# design.net
KiCad netlist of a schematic drawn in Altium Designer
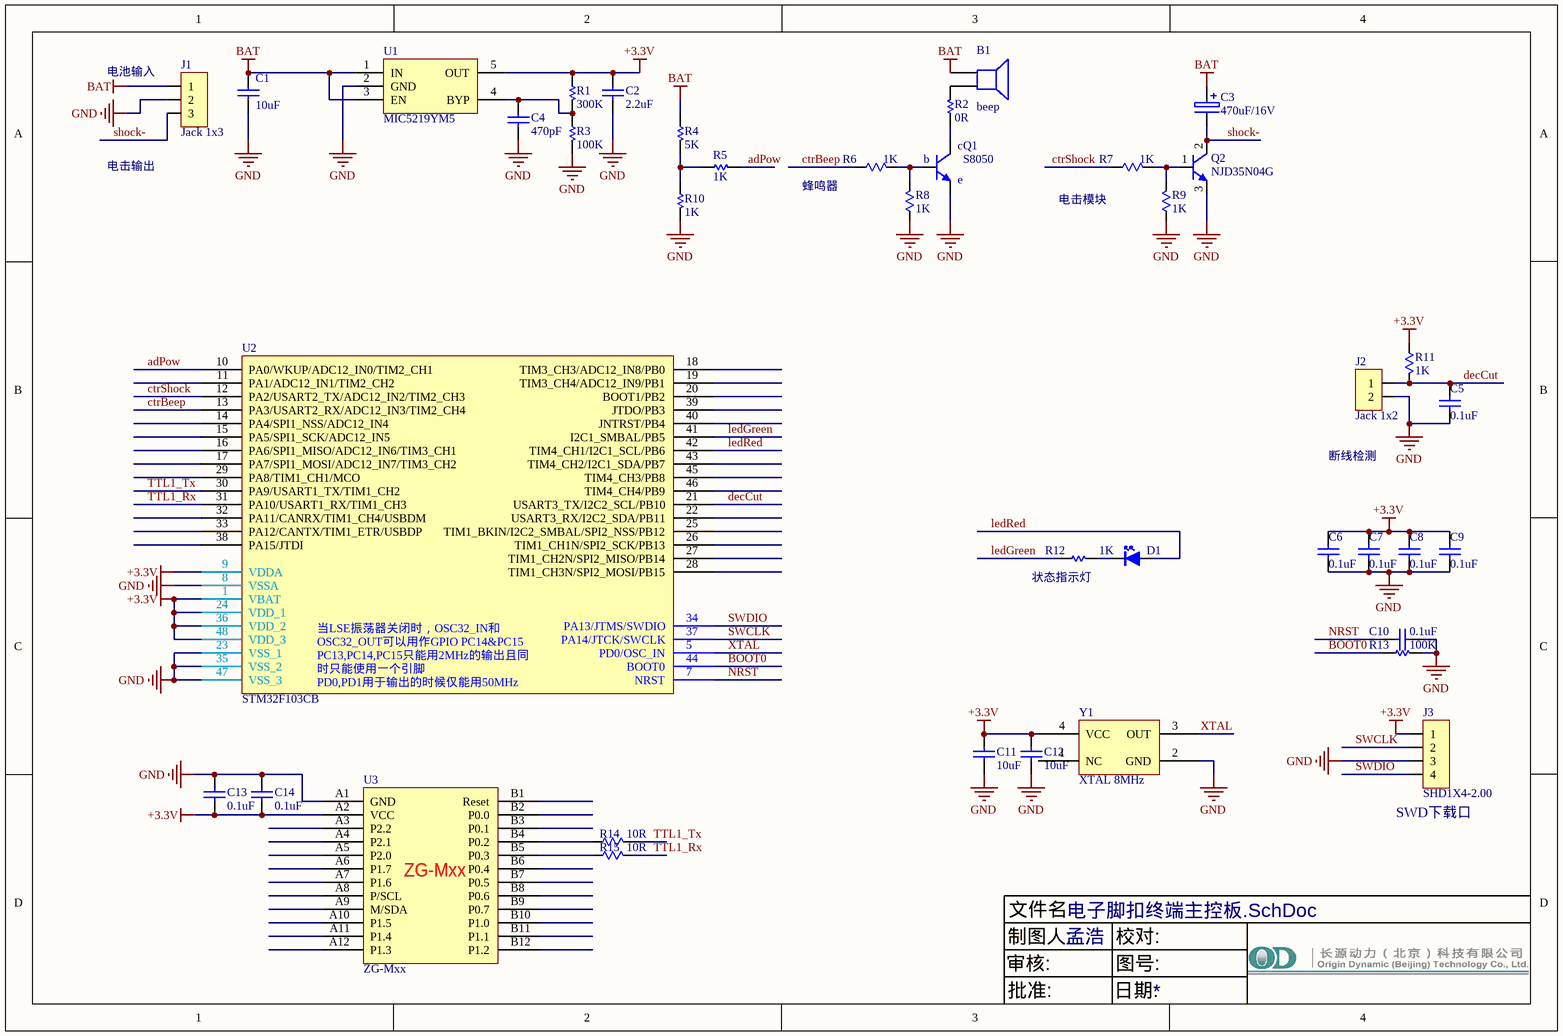
[diagram p0: 电子脚扣终端主控板.SchDoc]

(export (version "E")
  (design (tool "Eeschema 10.0.6"))
  (components
    (comp (ref "B1")
      (value "beep")
      (footprint "Jk1*2-2.0")
      (description "Loudspeaker")
      (fields (field (name "PUBLISHER") "Altium Limited"))
      (libsource (lib "Miscellaneous Devices") (part "Speaker"))
    )
    (comp (ref "C1") (value "10uF") (footprint "C0603") (libsource (lib "RLCYDF") (part "Cap Semi")))
    (comp (ref "C2")
      (value "2.2uF")
      (footprint "C0603")
      (description "CAP")
      (fields (field (name "PUBLISHER") "Altium Limited"))
      (libsource (lib "Passive Components Class") (part "CAP"))
    )
    (comp (ref "C3") (value "470uF/16V") (footprint "Jk1*2-2.0") (libsource (lib "RLCYDF") (part "Cap Poll")))
    (comp (ref "C4")
      (value "470pF")
      (footprint "C0603")
      (description "CAP")
      (fields (field (name "PUBLISHER") "Altium Limited"))
      (libsource (lib "Passive Components Class") (part "CAP"))
    )
    (comp (ref "C5") (value "0.1uF") (footprint "C0603") (libsource (lib "RLCYDF") (part "Cap Semi")))
    (comp (ref "C6") (value "0.1uF") (footprint "C0603") (libsource (lib "RLCYDF") (part "Cap Semi")))
    (comp (ref "C7") (value "0.1uF") (footprint "C0603") (libsource (lib "RLCYDF") (part "Cap Semi")))
    (comp (ref "C8") (value "0.1uF") (footprint "C0603") (libsource (lib "RLCYDF") (part "Cap Semi")))
    (comp (ref "C9") (value "0.1uF") (footprint "C0603") (libsource (lib "RLCYDF") (part "Cap Semi")))
    (comp (ref "C10") (value "0.1uF") (footprint "C0603") (libsource (lib "RLCYDF") (part "Cap Semi")))
    (comp (ref "C11") (value "10uF") (footprint "C0603") (libsource (lib "RLCYDF") (part "Cap Semi")))
    (comp (ref "C12") (value "10uF") (footprint "C0603") (libsource (lib "RLCYDF") (part "Cap Semi")))
    (comp (ref "C13")
      (value "0.1uF")
      (footprint "C0603")
      (description "Capacitor")
      (fields (field (name "PUBLISHER") "Altium Limited"))
      (libsource (lib "Miscellaneous Devices") (part "Cap"))
    )
    (comp (ref "C14")
      (value "0.1uF")
      (footprint "C0603")
      (description "Capacitor")
      (fields (field (name "PUBLISHER") "Altium Limited"))
      (libsource (lib "Miscellaneous Devices") (part "Cap"))
    )
    (comp (ref "D1")
      (value "LED")
      (footprint "Led-D3")
      (libsource (lib "Passive Components Class") (part "LED"))
    )
    (comp (ref "J1")
      (value "Jack 1x3")
      (footprint "Jk1*3-2.0")
      (description "插座")
      (libsource (lib "Connector") (part "Jack 1x3"))
    )
    (comp (ref "J2")
      (value "Jack 1x2")
      (footprint "Jk1*2-2.0")
      (description "插座")
      (libsource (lib "Connector") (part "Jack 1x2"))
    )
    (comp (ref "J3")
      (value "SHD1X4-2.00")
      (footprint "Jk1*4-2.0")
      (libsource (lib "Connector Class") (part "HEADER1X4"))
    )
    (comp (ref "Q1")
      (value "S8050")
      (footprint "chip:SOT-23")
      (description "NPN triode, 0.5A Max")
      (libsource (lib "RLCYDF") (part "S8050"))
    )
    (comp (ref "Q2") (value "NJD35N04G") (footprint "TO-252") (libsource (lib "ArmArmor") (part "MJD122")))
    (comp (ref "R1") (value "300K") (footprint "R0603") (libsource (lib "RLCYDF") (part "Res")))
    (comp (ref "R2") (value "0R") (footprint "R0603") (libsource (lib "RLCYDF") (part "Res")))
    (comp (ref "R3") (value "100K") (footprint "R0603") (libsource (lib "RLCYDF") (part "Res")))
    (comp (ref "R4") (value "5K") (footprint "R0603") (libsource (lib "RLCYDF") (part "Res")))
    (comp (ref "R5") (value "1K") (footprint "R0603") (libsource (lib "RLCYDF") (part "Res")))
    (comp (ref "R6")
      (value "1K")
      (footprint "R0603")
      (description "Resistor")
      (fields (field (name "PUBLISHER") "Altium Limited"))
      (libsource (lib "Passive Components Class") (part "RES"))
    )
    (comp (ref "R7")
      (value "1K")
      (footprint "R0603")
      (description "Resistor")
      (fields (field (name "PUBLISHER") "Altium Limited"))
      (libsource (lib "Passive Components Class") (part "RES"))
    )
    (comp (ref "R8")
      (value "1K")
      (footprint "R0603")
      (description "Resistor")
      (fields (field (name "PUBLISHER") "Altium Limited"))
      (libsource (lib "Passive Components Class") (part "RES"))
    )
    (comp (ref "R9")
      (value "1K")
      (footprint "R0603")
      (description "Resistor")
      (fields (field (name "PUBLISHER") "Altium Limited"))
      (libsource (lib "Passive Components Class") (part "RES"))
    )
    (comp (ref "R10") (value "1K") (footprint "R0603") (libsource (lib "RLCYDF") (part "Res")))
    (comp (ref "R11")
      (value "1K")
      (footprint "R0603")
      (description "Resistor")
      (fields (field (name "PUBLISHER") "Altium Limited"))
      (libsource (lib "Passive Components Class") (part "RES"))
    )
    (comp (ref "R12") (value "1K") (footprint "R0603") (libsource (lib "RLCYDF") (part "Res")))
    (comp (ref "R13") (value "100K") (footprint "R0603") (libsource (lib "RLCYDF") (part "Res")))
    (comp (ref "R14")
      (value "10R")
      (footprint "R0603")
      (description "Resistor")
      (fields (field (name "PUBLISHER") "Altium Limited"))
      (libsource (lib "UP-Robot") (part "Res"))
    )
    (comp (ref "R15")
      (value "10R")
      (footprint "R0603")
      (description "Resistor")
      (fields (field (name "PUBLISHER") "Altium Limited"))
      (libsource (lib "UP-Robot") (part "Res"))
    )
    (comp (ref "U1") (value "MIC5219YM5") (footprint "SOT-23-5") (libsource (lib "Power") (part "MIC5205")))
    (comp (ref "U2") (value "STM32F103CB") (footprint "LQF48") (libsource (lib "stm32") (part "STM32F103Cx")))
    (comp (ref "U3") (value "ZG-Mxx") (footprint "ZG-M0") (libsource (lib "ZG-Mxx") (part "ZG-Mxx")))
    (comp (ref "Y1") (value "XTAL 8MHz") (footprint "XTAL5032") (libsource (lib "Mic2805") (part "XTAL")))
  )
  (nets
    (net (code "1") (name "+3.3V") (class "Default")
      (node (ref "C11") (pin "2") (pinfunction "2_2") (pintype "passive"))
      (node (ref "C12") (pin "2") (pinfunction "2_2") (pintype "passive"))
      (node (ref "C13") (pin "1") (pinfunction "1_1") (pintype "passive"))
      (node (ref "C14") (pin "1") (pinfunction "1_1") (pintype "passive"))
      (node (ref "C2") (pin "1") (pinfunction "1_1") (pintype "passive"))
      (node (ref "C6") (pin "1") (pinfunction "1_1") (pintype "passive"))
      (node (ref "C7") (pin "1") (pinfunction "1_1") (pintype "passive"))
      (node (ref "C8") (pin "1") (pinfunction "1_1") (pintype "passive"))
      (node (ref "C9") (pin "1") (pinfunction "1_1") (pintype "passive"))
      (node (ref "J3") (pin "1") (pinfunction "1_1") (pintype "passive"))
      (node (ref "R1") (pin "1") (pinfunction "1_1") (pintype "passive"))
      (node (ref "R11") (pin "1") (pinfunction "1_1") (pintype "passive"))
      (node (ref "U1") (pin "5") (pinfunction "OUT_5") (pintype "passive"))
      (node (ref "U2") (pin "1") (pinfunction "VBAT_1") (pintype "power_in"))
      (node (ref "U2") (pin "24") (pinfunction "VDD_1_24") (pintype "power_in"))
      (node (ref "U2") (pin "36") (pinfunction "VDD_2_36") (pintype "power_in"))
      (node (ref "U2") (pin "48") (pinfunction "VDD_3_48") (pintype "power_in"))
      (node (ref "U2") (pin "9") (pinfunction "VDDA_9") (pintype "power_in"))
      (node (ref "U3") (pin "A2") (pinfunction "VCC_A2") (pintype "passive"))
      (node (ref "Y1") (pin "4") (pinfunction "VCC_4") (pintype "passive"))
    )
    (net (code "2") (name "/BOOT0") (class "Default")
      (node (ref "R13") (pin "1") (pinfunction "1_1") (pintype "passive"))
      (node (ref "U2") (pin "44") (pinfunction "BOOT0_44") (pintype "passive"))
    )
    (net (code "3") (name "/NRST") (class "Default")
      (node (ref "C10") (pin "1") (pinfunction "1_1") (pintype "passive"))
      (node (ref "U2") (pin "7") (pinfunction "NRST_7") (pintype "passive"))
    )
    (net (code "4") (name "/SWCLK") (class "Default")
      (node (ref "J3") (pin "2") (pinfunction "2_2") (pintype "passive"))
      (node (ref "U2") (pin "37") (pinfunction "PA14/JTCK/SWCLK_37") (pintype "passive"))
    )
    (net (code "5") (name "/SWDIO") (class "Default")
      (node (ref "J3") (pin "4") (pinfunction "4_4") (pintype "passive"))
      (node (ref "U2") (pin "34") (pinfunction "PA13/JTMS/SWDIO_34") (pintype "passive"))
    )
    (net (code "6") (name "/TTL1_Rx") (class "Default")
      (node (ref "R15") (pin "1") (pinfunction "1_1") (pintype "passive"))
      (node (ref "U2") (pin "31") (pinfunction "PA10/USART1_RX/TIM1_CH3_31") (pintype "passive"))
    )
    (net (code "7") (name "/TTL1_Tx") (class "Default")
      (node (ref "R14") (pin "1") (pinfunction "1_1") (pintype "passive"))
      (node (ref "U2") (pin "30") (pinfunction "PA9/USART1_TX/TIM1_CH2_30") (pintype "passive"))
    )
    (net (code "8") (name "/XTAL") (class "Default")
      (node (ref "U2") (pin "5") (pinfunction "PD0/OSC_IN_5") (pintype "passive"))
      (node (ref "Y1") (pin "3") (pinfunction "OUT_3") (pintype "passive"))
    )
    (net (code "9") (name "/adPow") (class "Default")
      (node (ref "R5") (pin "2") (pinfunction "2_2") (pintype "passive"))
      (node (ref "U2") (pin "10") (pinfunction "PA0/WKUP/ADC12_IN0/TIM2_CH1_10") (pintype "passive"))
    )
    (net (code "10") (name "/ctrBeep") (class "Default")
      (node (ref "R6") (pin "1") (pinfunction "1_1") (pintype "passive"))
      (node (ref "U2") (pin "13") (pinfunction "PA3/USART2_RX/ADC12_IN3/TIM2_CH4_13") (pintype "passive"))
    )
    (net (code "11") (name "/ctrShock") (class "Default")
      (node (ref "R7") (pin "1") (pinfunction "1_1") (pintype "passive"))
      (node (ref "U2") (pin "12") (pinfunction "PA2/USART2_TX/ADC12_IN2/TIM2_CH3_12") (pintype "passive"))
    )
    (net (code "12") (name "/decCut") (class "Default")
      (node (ref "C5") (pin "1") (pinfunction "1_1") (pintype "passive"))
      (node (ref "J2") (pin "1") (pinfunction "1_1") (pintype "passive"))
      (node (ref "R11") (pin "2") (pinfunction "2_2") (pintype "passive"))
      (node (ref "U2") (pin "21") (pinfunction "USART3_TX/I2C2_SCL/PB10_21") (pintype "passive"))
    )
    (net (code "13") (name "/ledGreen") (class "Default")
      (node (ref "R12") (pin "1") (pinfunction "1_1") (pintype "passive"))
      (node (ref "U2") (pin "41") (pinfunction "I2C1_SMBAL/PB5_41") (pintype "passive"))
    )
    (net (code "14") (name "/ledRed") (class "Default")
      (node (ref "D1") (pin "1") (pinfunction "A_1") (pintype "passive"))
      (node (ref "U2") (pin "42") (pinfunction "TIM4_CH1/I2C1_SCL/PB6_42") (pintype "passive"))
    )
    (net (code "15") (name "/shock-") (class "Default")
      (node (ref "C3") (pin "2") (pinfunction "2_2") (pintype "passive"))
      (node (ref "J1") (pin "3") (pinfunction "3_3") (pintype "passive"))
      (node (ref "Q2") (pin "2") (pinfunction "C_2") (pintype "passive"))
    )
    (net (code "16") (name "BAT") (class "Default")
      (node (ref "B1") (pin "1") (pinfunction "1_1") (pintype "passive"))
      (node (ref "C1") (pin "2") (pinfunction "2_2") (pintype "passive"))
      (node (ref "C3") (pin "1") (pinfunction "1_1") (pintype "passive"))
      (node (ref "J1") (pin "1") (pinfunction "1_1") (pintype "passive"))
      (node (ref "R4") (pin "1") (pinfunction "1_1") (pintype "passive"))
      (node (ref "U1") (pin "1") (pinfunction "IN_1") (pintype "passive"))
      (node (ref "U1") (pin "3") (pinfunction "EN_3") (pintype "passive"))
    )
    (net (code "17") (name "GND") (class "Default")
      (node (ref "C1") (pin "1") (pinfunction "1_1") (pintype "passive"))
      (node (ref "C10") (pin "2") (pinfunction "2_2") (pintype "passive"))
      (node (ref "C11") (pin "1") (pinfunction "1_1") (pintype "passive"))
      (node (ref "C12") (pin "1") (pinfunction "1_1") (pintype "passive"))
      (node (ref "C13") (pin "2") (pinfunction "2_2") (pintype "passive"))
      (node (ref "C14") (pin "2") (pinfunction "2_2") (pintype "passive"))
      (node (ref "C2") (pin "2") (pinfunction "2_2") (pintype "passive"))
      (node (ref "C4") (pin "2") (pinfunction "2_2") (pintype "passive"))
      (node (ref "C5") (pin "2") (pinfunction "2_2") (pintype "passive"))
      (node (ref "C6") (pin "2") (pinfunction "2_2") (pintype "passive"))
      (node (ref "C7") (pin "2") (pinfunction "2_2") (pintype "passive"))
      (node (ref "C8") (pin "2") (pinfunction "2_2") (pintype "passive"))
      (node (ref "C9") (pin "2") (pinfunction "2_2") (pintype "passive"))
      (node (ref "J1") (pin "2") (pinfunction "2_2") (pintype "passive"))
      (node (ref "J2") (pin "2") (pinfunction "2_2") (pintype "passive"))
      (node (ref "J3") (pin "3") (pinfunction "3_3") (pintype "passive"))
      (node (ref "Q1") (pin "2") (pinfunction "e_2") (pintype "passive"))
      (node (ref "Q2") (pin "3") (pinfunction "E_3") (pintype "passive"))
      (node (ref "R10") (pin "2") (pinfunction "2_2") (pintype "passive"))
      (node (ref "R13") (pin "2") (pinfunction "2_2") (pintype "passive"))
      (node (ref "R3") (pin "2") (pinfunction "2_2") (pintype "passive"))
      (node (ref "R8") (pin "1") (pinfunction "1_1") (pintype "passive"))
      (node (ref "R9") (pin "1") (pinfunction "1_1") (pintype "passive"))
      (node (ref "U1") (pin "2") (pinfunction "GND_2") (pintype "passive"))
      (node (ref "U2") (pin "23") (pinfunction "VSS_1_23") (pintype "power_in"))
      (node (ref "U2") (pin "35") (pinfunction "VSS_2_35") (pintype "power_in"))
      (node (ref "U2") (pin "47") (pinfunction "VSS_3_47") (pintype "power_in"))
      (node (ref "U2") (pin "8") (pinfunction "VSSA_8") (pintype "power_in"))
      (node (ref "U3") (pin "A1") (pinfunction "GND_A1") (pintype "passive"))
      (node (ref "Y1") (pin "2") (pinfunction "GND_2") (pintype "passive"))
    )
    (net (code "18") (name "Net-(B1-Pad2)") (class "Default")
      (node (ref "B1") (pin "2") (pinfunction "2_2") (pintype "passive"))
      (node (ref "R2") (pin "2") (pinfunction "2_2") (pintype "passive"))
    )
    (net (code "19") (name "Net-(D1-K)") (class "Default")
      (node (ref "D1") (pin "2") (pinfunction "K_2") (pintype "passive"))
      (node (ref "R12") (pin "2") (pinfunction "2_2") (pintype "passive"))
    )
    (net (code "20") (name "Net-(Q1-b)") (class "Default")
      (node (ref "Q1") (pin "1") (pinfunction "b_1") (pintype "passive"))
      (node (ref "R6") (pin "2") (pinfunction "2_2") (pintype "passive"))
      (node (ref "R8") (pin "2") (pinfunction "2_2") (pintype "passive"))
    )
    (net (code "21") (name "Net-(Q1-c)") (class "Default")
      (node (ref "Q1") (pin "3") (pinfunction "c_3") (pintype "passive"))
      (node (ref "R2") (pin "1") (pinfunction "1_1") (pintype "passive"))
    )
    (net (code "22") (name "Net-(Q2-B)") (class "Default")
      (node (ref "Q2") (pin "1") (pinfunction "B_1") (pintype "passive"))
      (node (ref "R7") (pin "2") (pinfunction "2_2") (pintype "passive"))
      (node (ref "R9") (pin "2") (pinfunction "2_2") (pintype "passive"))
    )
    (net (code "23") (name "Net-(R10-Pad1)") (class "Default")
      (node (ref "R10") (pin "1") (pinfunction "1_1") (pintype "passive"))
      (node (ref "R4") (pin "2") (pinfunction "2_2") (pintype "passive"))
      (node (ref "R5") (pin "1") (pinfunction "1_1") (pintype "passive"))
    )
    (net (code "24") (name "Net-(U1-BYP)") (class "Default")
      (node (ref "C4") (pin "1") (pinfunction "1_1") (pintype "passive"))
      (node (ref "R1") (pin "2") (pinfunction "2_2") (pintype "passive"))
      (node (ref "R3") (pin "1") (pinfunction "1_1") (pintype "passive"))
      (node (ref "U1") (pin "4") (pinfunction "BYP_4") (pintype "passive"))
    )
    (net (code "25") (name "Net-(U3-P0.2)") (class "Default")
      (node (ref "R14") (pin "2") (pinfunction "2_2") (pintype "passive"))
      (node (ref "U3") (pin "B4") (pinfunction "P0.2_B4") (pintype "passive"))
    )
    (net (code "26") (name "Net-(U3-P0.3)") (class "Default")
      (node (ref "R15") (pin "2") (pinfunction "2_2") (pintype "passive"))
      (node (ref "U3") (pin "B5") (pinfunction "P0.3_B5") (pintype "passive"))
    )
    (net (code "27") (name "unconnected-(U2-BOOT1{slash}PB2-Pad20)") (class "Default")
      (node (ref "U2") (pin "20") (pinfunction "BOOT1/PB2_20") (pintype "passive"))
    )
    (net (code "28") (name "unconnected-(U2-JNTRST{slash}PB4-Pad40)") (class "Default")
      (node (ref "U2") (pin "40") (pinfunction "JNTRST/PB4_40") (pintype "passive"))
    )
    (net (code "29") (name "unconnected-(U2-JTDO{slash}PB3-Pad39)") (class "Default")
      (node (ref "U2") (pin "39") (pinfunction "JTDO/PB3_39") (pintype "passive"))
    )
    (net (code "30") (name "unconnected-(U2-PA1{slash}ADC12_IN1{slash}TIM2_CH2-Pad11)") (class "Default")
      (node (ref "U2") (pin "11") (pinfunction "PA1/ADC12_IN1/TIM2_CH2_11") (pintype "passive"))
    )
    (net (code "31") (name "unconnected-(U2-PA4{slash}SPI1_NSS{slash}ADC12_IN4-Pad14)") (class "Default")
      (node (ref "U2") (pin "14") (pinfunction "PA4/SPI1_NSS/ADC12_IN4_14") (pintype "passive"))
    )
    (net (code "32") (name "unconnected-(U2-PA5{slash}SPI1_SCK{slash}ADC12_IN5-Pad15)") (class "Default")
      (node (ref "U2") (pin "15") (pinfunction "PA5/SPI1_SCK/ADC12_IN5_15") (pintype "passive"))
    )
    (net (code "33") (name "unconnected-(U2-PA6{slash}SPI1_MISO{slash}ADC12_IN6{slash}TIM3_CH1-Pad16)") (class "Default")
      (node (ref "U2") (pin "16") (pinfunction "PA6/SPI1_MISO/ADC12_IN6/TIM3_CH1_16") (pintype "passive"))
    )
    (net (code "34") (name "unconnected-(U2-PA7{slash}SPI1_MOSI{slash}ADC12_IN7{slash}TIM3_CH2-Pad17)") (class "Default")
      (node (ref "U2") (pin "17") (pinfunction "PA7/SPI1_MOSI/ADC12_IN7/TIM3_CH2_17") (pintype "passive"))
    )
    (net (code "35") (name "unconnected-(U2-PA8{slash}TIM1_CH1{slash}MCO-Pad29)") (class "Default")
      (node (ref "U2") (pin "29") (pinfunction "PA8/TIM1_CH1/MCO_29") (pintype "passive"))
    )
    (net (code "36") (name "unconnected-(U2-PA11{slash}CANRX{slash}TIM1_CH4{slash}USBDM-Pad32)") (class "Default")
      (node (ref "U2") (pin "32") (pinfunction "PA11/CANRX/TIM1_CH4/USBDM_32") (pintype "passive"))
    )
    (net (code "37") (name "unconnected-(U2-PA12{slash}CANTX{slash}TIM1_ETR{slash}USBDP-Pad33)") (class "Default")
      (node (ref "U2") (pin "33") (pinfunction "PA12/CANTX/TIM1_ETR/USBDP_33") (pintype "passive"))
    )
    (net (code "38") (name "unconnected-(U2-PA15{slash}JTDI-Pad38)") (class "Default")
      (node (ref "U2") (pin "38") (pinfunction "PA15/JTDI_38") (pintype "passive"))
    )
    (net (code "39") (name "unconnected-(U2-PC13-TAMPER-RTC-Pad2)") (class "Default")
      (node (ref "U2") (pin "2") (pinfunction "PC13-TAMPER-RTC_2") (pintype "passive"))
    )
    (net (code "40") (name "unconnected-(U2-PC14-OSC32_IN-Pad3)") (class "Default")
      (node (ref "U2") (pin "3") (pinfunction "PC14-OSC32_IN_3") (pintype "passive"))
    )
    (net (code "41") (name "unconnected-(U2-PC15-OSC32_OUT-Pad4)") (class "Default")
      (node (ref "U2") (pin "4") (pinfunction "PC15-OSC32_OUT_4") (pintype "passive"))
    )
    (net (code "42") (name "unconnected-(U2-PD1{slash}OSC_OUT-Pad6)") (class "Default")
      (node (ref "U2") (pin "6") (pinfunction "PD1/OSC_OUT_6") (pintype "passive"))
    )
    (net (code "43") (name "unconnected-(U2-TIM1_BKIN{slash}I2C2_SMBAL{slash}SPI2_NSS{slash}PB12-Pad25)") (class "Default")
      (node (ref "U2") (pin "25") (pinfunction "TIM1_BKIN/I2C2_SMBAL/SPI2_NSS/PB12_25") (pintype "passive"))
    )
    (net (code "44") (name "unconnected-(U2-TIM1_CH1N{slash}SPI2_SCK{slash}PB13-Pad26)") (class "Default")
      (node (ref "U2") (pin "26") (pinfunction "TIM1_CH1N/SPI2_SCK/PB13_26") (pintype "passive"))
    )
    (net (code "45") (name "unconnected-(U2-TIM1_CH2N{slash}SPI2_MISO{slash}PB14-Pad27)") (class "Default")
      (node (ref "U2") (pin "27") (pinfunction "TIM1_CH2N/SPI2_MISO/PB14_27") (pintype "passive"))
    )
    (net (code "46") (name "unconnected-(U2-TIM1_CH3N{slash}SPI2_MOSI{slash}PB15-Pad28)") (class "Default")
      (node (ref "U2") (pin "28") (pinfunction "TIM1_CH3N/SPI2_MOSI/PB15_28") (pintype "passive"))
    )
    (net (code "47") (name "unconnected-(U2-TIM3_CH3{slash}ADC12_IN8{slash}PB0-Pad18)") (class "Default")
      (node (ref "U2") (pin "18") (pinfunction "TIM3_CH3/ADC12_IN8/PB0_18") (pintype "passive"))
    )
    (net (code "48") (name "unconnected-(U2-TIM3_CH4{slash}ADC12_IN9{slash}PB1-Pad19)") (class "Default")
      (node (ref "U2") (pin "19") (pinfunction "TIM3_CH4/ADC12_IN9/PB1_19") (pintype "passive"))
    )
    (net (code "49") (name "unconnected-(U2-TIM4_CH2{slash}I2C1_SDA{slash}PB7-Pad43)") (class "Default")
      (node (ref "U2") (pin "43") (pinfunction "TIM4_CH2/I2C1_SDA/PB7_43") (pintype "passive"))
    )
    (net (code "50") (name "unconnected-(U2-TIM4_CH3{slash}PB8-Pad45)") (class "Default")
      (node (ref "U2") (pin "45") (pinfunction "TIM4_CH3/PB8_45") (pintype "passive"))
    )
    (net (code "51") (name "unconnected-(U2-TIM4_CH4{slash}PB9-Pad46)") (class "Default")
      (node (ref "U2") (pin "46") (pinfunction "TIM4_CH4/PB9_46") (pintype "passive"))
    )
    (net (code "52") (name "unconnected-(U2-USART3_RX{slash}I2C2_SDA{slash}PB11-Pad22)") (class "Default")
      (node (ref "U2") (pin "22") (pinfunction "USART3_RX/I2C2_SDA/PB11_22") (pintype "passive"))
    )
    (net (code "53") (name "unconnected-(U3-M{slash}SDA-PadA9)") (class "Default")
      (node (ref "U3") (pin "A9") (pinfunction "M/SDA_A9") (pintype "passive"))
    )
    (net (code "54") (name "unconnected-(U3-P0.0-PadB2)") (class "Default")
      (node (ref "U3") (pin "B2") (pinfunction "P0.0_B2") (pintype "passive"))
    )
    (net (code "55") (name "unconnected-(U3-P0.1-PadB3)") (class "Default")
      (node (ref "U3") (pin "B3") (pinfunction "P0.1_B3") (pintype "passive"))
    )
    (net (code "56") (name "unconnected-(U3-P0.4-PadB6)") (class "Default")
      (node (ref "U3") (pin "B6") (pinfunction "P0.4_B6") (pintype "passive"))
    )
    (net (code "57") (name "unconnected-(U3-P0.5-PadB7)") (class "Default")
      (node (ref "U3") (pin "B7") (pinfunction "P0.5_B7") (pintype "passive"))
    )
    (net (code "58") (name "unconnected-(U3-P0.6-PadB8)") (class "Default")
      (node (ref "U3") (pin "B8") (pinfunction "P0.6_B8") (pintype "passive"))
    )
    (net (code "59") (name "unconnected-(U3-P0.7-PadB9)") (class "Default")
      (node (ref "U3") (pin "B9") (pinfunction "P0.7_B9") (pintype "passive"))
    )
    (net (code "60") (name "unconnected-(U3-P1.0-PadB10)") (class "Default")
      (node (ref "U3") (pin "B10") (pinfunction "P1.0_B10") (pintype "passive"))
    )
    (net (code "61") (name "unconnected-(U3-P1.1-PadB11)") (class "Default")
      (node (ref "U3") (pin "B11") (pinfunction "P1.1_B11") (pintype "passive"))
    )
    (net (code "62") (name "unconnected-(U3-P1.2-PadB12)") (class "Default")
      (node (ref "U3") (pin "B12") (pinfunction "P1.2_B12") (pintype "passive"))
    )
    (net (code "63") (name "unconnected-(U3-P1.3-PadA12)") (class "Default")
      (node (ref "U3") (pin "A12") (pinfunction "P1.3_A12") (pintype "passive"))
    )
    (net (code "64") (name "unconnected-(U3-P1.4-PadA11)") (class "Default")
      (node (ref "U3") (pin "A11") (pinfunction "P1.4_A11") (pintype "passive"))
    )
    (net (code "65") (name "unconnected-(U3-P1.5-PadA10)") (class "Default")
      (node (ref "U3") (pin "A10") (pinfunction "P1.5_A10") (pintype "passive"))
    )
    (net (code "66") (name "unconnected-(U3-P1.6-PadA7)") (class "Default")
      (node (ref "U3") (pin "A7") (pinfunction "P1.6_A7") (pintype "passive"))
    )
    (net (code "67") (name "unconnected-(U3-P1.7-PadA6)") (class "Default")
      (node (ref "U3") (pin "A6") (pinfunction "P1.7_A6") (pintype "passive"))
    )
    (net (code "68") (name "unconnected-(U3-P2.0-PadA5)") (class "Default")
      (node (ref "U3") (pin "A5") (pinfunction "P2.0_A5") (pintype "passive"))
    )
    (net (code "69") (name "unconnected-(U3-P2.1-PadA4)") (class "Default")
      (node (ref "U3") (pin "A4") (pinfunction "P2.1_A4") (pintype "passive"))
    )
    (net (code "70") (name "unconnected-(U3-P2.2-PadA3)") (class "Default")
      (node (ref "U3") (pin "A3") (pinfunction "P2.2_A3") (pintype "passive"))
    )
    (net (code "71") (name "unconnected-(U3-P{slash}SCL-PadA8)") (class "Default")
      (node (ref "U3") (pin "A8") (pinfunction "P/SCL_A8") (pintype "passive"))
    )
    (net (code "72") (name "unconnected-(U3-Reset-PadB1)") (class "Default")
      (node (ref "U3") (pin "B1") (pinfunction "Reset_B1") (pintype "passive"))
    )
    (net (code "73") (name "unconnected-(Y1-NC-Pad1)") (class "Default")
      (node (ref "Y1") (pin "1") (pinfunction "NC_1") (pintype "passive"))
    )
  )
)
